# AS7263.net
KiCad netlist of a schematic drawn in Altium Designer
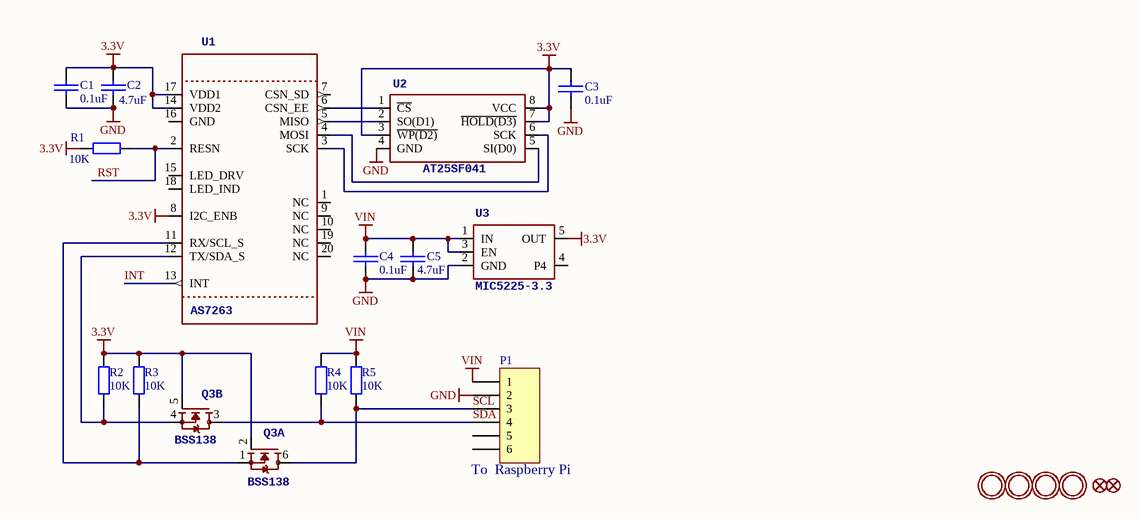
[diagram p0: AS7263.SchDoc]

(export (version "E")
  (design (tool "Eeschema 10.0.6"))
  (components
    (comp (ref "C1") (value "0.1uF") (footprint "0805") (libsource (lib "*") (part "CAP")))
    (comp (ref "C2") (value "4.7uF") (footprint "0805") (libsource (lib "*") (part "CAP")))
    (comp (ref "C3") (value "0.1uF") (footprint "0805") (libsource (lib "*") (part "CAP")))
    (comp (ref "C4") (value "0.1uF") (footprint "0805") (libsource (lib "*") (part "CAP")))
    (comp (ref "C5") (value "4.7uF") (footprint "0805") (libsource (lib "*") (part "CAP")))
    (comp (ref "FID2")
      (value "FIDUCIAL_1MM")
      (footprint "FIDUCIAL_1MM")
      (description "<b>Fiducial Alignment Points</b>\n<p>Various fiducial points for machine vision alignment.</p>")
      (libsource (lib "microbuilder") (part "FIDUCIAL_1MM"))
    )
    (comp (ref "FID3")
      (value "FIDUCIAL_1MM")
      (footprint "FIDUCIAL_1MM")
      (description "<b>Fiducial Alignment Points</b>\n<p>Various fiducial points for machine vision alignment.</p>")
      (libsource (lib "microbuilder") (part "FIDUCIAL_1MM"))
    )
    (comp (ref "P1")
      (value "To  Raspberry Pi")
      (footprint "HDR1X6")
      (description "Header, 6-Pin")
      (fields (field (name "PUBLISHER") "Altium Limited"))
      (libsource (lib "Miscellaneous Connectors") (part "Header 6"))
    )
    (comp (ref "Q3")
      (value "BSS138")
      (footprint "SOT363")
      (libsource (lib "microbuilder") (part "MOSFET-N_DUAL"))
    )
    (comp (ref "R1")
      (value "10K")
      (footprint "0805")
      (description "Resistor")
      (fields (field (name "PUBLISHER") "Altium Limited"))
      (libsource (lib "") (part "Res2_1"))
    )
    (comp (ref "R2")
      (value "10K")
      (footprint "0805")
      (description "Resistor")
      (fields (field (name "PUBLISHER") "Altium Limited"))
      (libsource (lib "Miscellaneous Devices") (part "Res2"))
    )
    (comp (ref "R3")
      (value "10K")
      (footprint "0805")
      (description "Resistor")
      (fields (field (name "PUBLISHER") "Altium Limited"))
      (libsource (lib "Miscellaneous Devices") (part "Res2"))
    )
    (comp (ref "R4")
      (value "10K")
      (footprint "0805")
      (description "Resistor")
      (fields (field (name "PUBLISHER") "Altium Limited"))
      (libsource (lib "Miscellaneous Devices") (part "Res2"))
    )
    (comp (ref "R5")
      (value "10K")
      (footprint "0805")
      (description "Resistor")
      (fields (field (name "PUBLISHER") "Altium Limited"))
      (libsource (lib "Miscellaneous Devices") (part "Res2"))
    )
    (comp (ref "U$2")
      (value "MOUNTINGHOLE2.5")
      (footprint "MOUNTINGHOLE_2.5_PLATED")
      (description "<b>Mounting Hole</b>\n<p>For #2 screws (0.086\"/2.18mm width, 0.094\"/2.4mm hole) use 2.5mm</p>")
      (libsource (lib "microbuilder") (part "MOUNTINGHOLE2.5"))
    )
    (comp (ref "U$3")
      (value "MOUNTINGHOLE2.5")
      (footprint "MOUNTINGHOLE_2.5_PLATED")
      (description "<b>Mounting Hole</b>\n<p>For #2 screws (0.086\"/2.18mm width, 0.094\"/2.4mm hole) use 2.5mm</p>")
      (libsource (lib "microbuilder") (part "MOUNTINGHOLE2.5"))
    )
    (comp (ref "U$22")
      (value "MOUNTINGHOLE2.5")
      (footprint "MOUNTINGHOLE_2.5_PLATED")
      (description "<b>Mounting Hole</b>\n<p>For #2 screws (0.086\"/2.18mm width, 0.094\"/2.4mm hole) use 2.5mm</p>")
      (libsource (lib "microbuilder") (part "MOUNTINGHOLE2.5"))
    )
    (comp (ref "U$23")
      (value "MOUNTINGHOLE2.5")
      (footprint "MOUNTINGHOLE_2.5_PLATED")
      (description "<b>Mounting Hole</b>\n<p>For #2 screws (0.086\"/2.18mm width, 0.094\"/2.4mm hole) use 2.5mm</p>")
      (libsource (lib "microbuilder") (part "MOUNTINGHOLE2.5"))
    )
    (comp (ref "U1")
      (value "AS7263")
      (footprint "AS726X_LGA20")
      (description "<p><b>AS726x Spectral Sensor</b></p>")
      (libsource (lib "microbuilder") (part "AS726X_SPECTRAL"))
    )
    (comp (ref "U2")
      (value "AT25SF041")
      (footprint "SO08")
      (libsource (lib "SparkFun-IC-Memory") (part "AT25SF041"))
    )
    (comp (ref "U3")
      (value "MIC5225-3.3")
      (footprint "SOT23-5")
      (libsource (lib "microbuilder") (part "VREG_SOT23-5"))
    )
  )
  (nets
    (net (code "1") (name "/INT") (class "Default")
      (node (ref "U1") (pin "13") (pinfunction "INT_13") (pintype "output"))
    )
    (net (code "2") (name "/RST") (class "Default")
      (node (ref "R1") (pin "1") (pinfunction "1_1") (pintype "passive"))
      (node (ref "U1") (pin "2") (pinfunction "RESN_2") (pintype "passive"))
    )
    (net (code "3") (name "/SCL") (class "Default")
      (node (ref "P1") (pin "3") (pinfunction "3_3") (pintype "passive"))
      (node (ref "Q3") (pin "6") (pinfunction "D_6") (pintype "passive"))
      (node (ref "R5") (pin "2") (pinfunction "2_2") (pintype "passive"))
    )
    (net (code "4") (name "/SDA") (class "Default")
      (node (ref "P1") (pin "4") (pinfunction "4_4") (pintype "passive"))
      (node (ref "Q3") (pin "3") (pinfunction "D_3") (pintype "passive"))
      (node (ref "R4") (pin "2") (pinfunction "2_2") (pintype "passive"))
    )
    (net (code "5") (name "3.3V") (class "Default")
      (node (ref "C1") (pin "1") (pintype "passive"))
      (node (ref "C2") (pin "1") (pintype "passive"))
      (node (ref "C3") (pin "1") (pintype "passive"))
      (node (ref "Q3") (pin "2") (pinfunction "G_2") (pintype "passive"))
      (node (ref "Q3") (pin "5") (pinfunction "G_5") (pintype "passive"))
      (node (ref "R1") (pin "2") (pinfunction "2_2") (pintype "passive"))
      (node (ref "R2") (pin "1") (pinfunction "1_1") (pintype "passive"))
      (node (ref "R3") (pin "1") (pinfunction "1_1") (pintype "passive"))
      (node (ref "U1") (pin "14") (pinfunction "VDD2_14") (pintype "power_in"))
      (node (ref "U1") (pin "17") (pinfunction "VDD1_17") (pintype "power_in"))
      (node (ref "U1") (pin "8") (pinfunction "I2C_ENB_8") (pintype "passive"))
      (node (ref "U2") (pin "3") (pinfunction "~{WP(D2)}_3") (pintype "passive"))
      (node (ref "U2") (pin "7") (pinfunction "~{HOLD(D3)}_7") (pintype "passive"))
      (node (ref "U2") (pin "8") (pinfunction "VCC_8") (pintype "passive"))
      (node (ref "U3") (pin "5") (pinfunction "OUT_5") (pintype "open_emitter"))
    )
    (net (code "6") (name "GND") (class "Default")
      (node (ref "C1") (pin "2") (pintype "passive"))
      (node (ref "C2") (pin "2") (pintype "passive"))
      (node (ref "C3") (pin "2") (pintype "passive"))
      (node (ref "C4") (pin "2") (pintype "passive"))
      (node (ref "C5") (pin "2") (pintype "passive"))
      (node (ref "P1") (pin "2") (pinfunction "2_2") (pintype "passive"))
      (node (ref "U2") (pin "4") (pinfunction "GND_4") (pintype "passive"))
      (node (ref "U3") (pin "2") (pinfunction "GND_2") (pintype "power_in"))
    )
    (net (code "7") (name "Net-(Q3A-S)") (class "Default")
      (node (ref "Q3") (pin "1") (pinfunction "S_1") (pintype "passive"))
      (node (ref "R3") (pin "2") (pinfunction "2_2") (pintype "passive"))
      (node (ref "U1") (pin "11") (pinfunction "RX/SCL_S_11") (pintype "passive"))
    )
    (net (code "8") (name "Net-(Q3B-S)") (class "Default")
      (node (ref "Q3") (pin "4") (pinfunction "S_4") (pintype "passive"))
      (node (ref "R2") (pin "2") (pinfunction "2_2") (pintype "passive"))
      (node (ref "U1") (pin "12") (pinfunction "TX/SDA_S_12") (pintype "passive"))
    )
    (net (code "9") (name "Net-(U1-CSN_EE)") (class "Default")
      (node (ref "U1") (pin "6") (pinfunction "CSN_EE_6") (pintype "output"))
      (node (ref "U2") (pin "1") (pinfunction "~{CS}_1") (pintype "passive"))
    )
    (net (code "10") (name "Net-(U1-MISO)") (class "Default")
      (node (ref "U1") (pin "5") (pinfunction "MISO_5") (pintype "output"))
      (node (ref "U2") (pin "2") (pinfunction "SO(D1)_2") (pintype "passive"))
    )
    (net (code "11") (name "Net-(U1-MOSI)") (class "Default")
      (node (ref "U1") (pin "4") (pinfunction "MOSI_4") (pintype "passive"))
      (node (ref "U2") (pin "5") (pinfunction "SI(D0)_5") (pintype "passive"))
    )
    (net (code "12") (name "Net-(U1-SCK)") (class "Default")
      (node (ref "U1") (pin "3") (pinfunction "SCK_3") (pintype "passive"))
      (node (ref "U2") (pin "6") (pinfunction "SCK_6") (pintype "passive"))
    )
    (net (code "13") (name "VIN") (class "Default")
      (node (ref "C4") (pin "1") (pintype "passive"))
      (node (ref "C5") (pin "1") (pintype "passive"))
      (node (ref "P1") (pin "1") (pinfunction "1_1") (pintype "passive"))
      (node (ref "R4") (pin "1") (pinfunction "1_1") (pintype "passive"))
      (node (ref "R5") (pin "1") (pinfunction "1_1") (pintype "passive"))
      (node (ref "U3") (pin "1") (pinfunction "IN_1") (pintype "power_in"))
      (node (ref "U3") (pin "3") (pinfunction "EN_3") (pintype "passive"))
    )
    (net (code "14") (name "unconnected-(P1-Pad5)") (class "Default")
      (node (ref "P1") (pin "5") (pinfunction "5_5") (pintype "passive"))
    )
    (net (code "15") (name "unconnected-(P1-Pad6)") (class "Default")
      (node (ref "P1") (pin "6") (pinfunction "6_6") (pintype "passive"))
    )
    (net (code "16") (name "unconnected-(U1-CSN_SD-Pad7)") (class "Default")
      (node (ref "U1") (pin "7") (pinfunction "CSN_SD_7") (pintype "output"))
    )
    (net (code "17") (name "unconnected-(U1-GND-Pad16)") (class "Default")
      (node (ref "U1") (pin "16") (pinfunction "GND_16") (pintype "power_in"))
    )
    (net (code "18") (name "unconnected-(U1-LED_DRV-Pad15)") (class "Default")
      (node (ref "U1") (pin "15") (pinfunction "LED_DRV_15") (pintype "passive"))
    )
    (net (code "19") (name "unconnected-(U1-LED_IND-Pad18)") (class "Default")
      (node (ref "U1") (pin "18") (pinfunction "LED_IND_18") (pintype "passive"))
    )
    (net (code "20") (name "unconnected-(U1-NC-Pad1)") (class "Default")
      (node (ref "U1") (pin "1") (pinfunction "NC_1") (pintype "passive"))
    )
    (net (code "21") (name "unconnected-(U1-NC-Pad9)") (class "Default")
      (node (ref "U1") (pin "9") (pinfunction "NC_9") (pintype "passive"))
    )
    (net (code "22") (name "unconnected-(U1-NC-Pad10)") (class "Default")
      (node (ref "U1") (pin "10") (pinfunction "NC_10") (pintype "passive"))
    )
    (net (code "23") (name "unconnected-(U1-NC-Pad19)") (class "Default")
      (node (ref "U1") (pin "19") (pinfunction "NC_19") (pintype "passive"))
    )
    (net (code "24") (name "unconnected-(U1-NC-Pad20)") (class "Default")
      (node (ref "U1") (pin "20") (pinfunction "NC_20") (pintype "passive"))
    )
    (net (code "25") (name "unconnected-(U3-P4-Pad4)") (class "Default")
      (node (ref "U3") (pin "4") (pinfunction "P4_4") (pintype "passive"))
    )
  )
)
